# Register.net
KiCad netlist of a schematic drawn in EAGLE
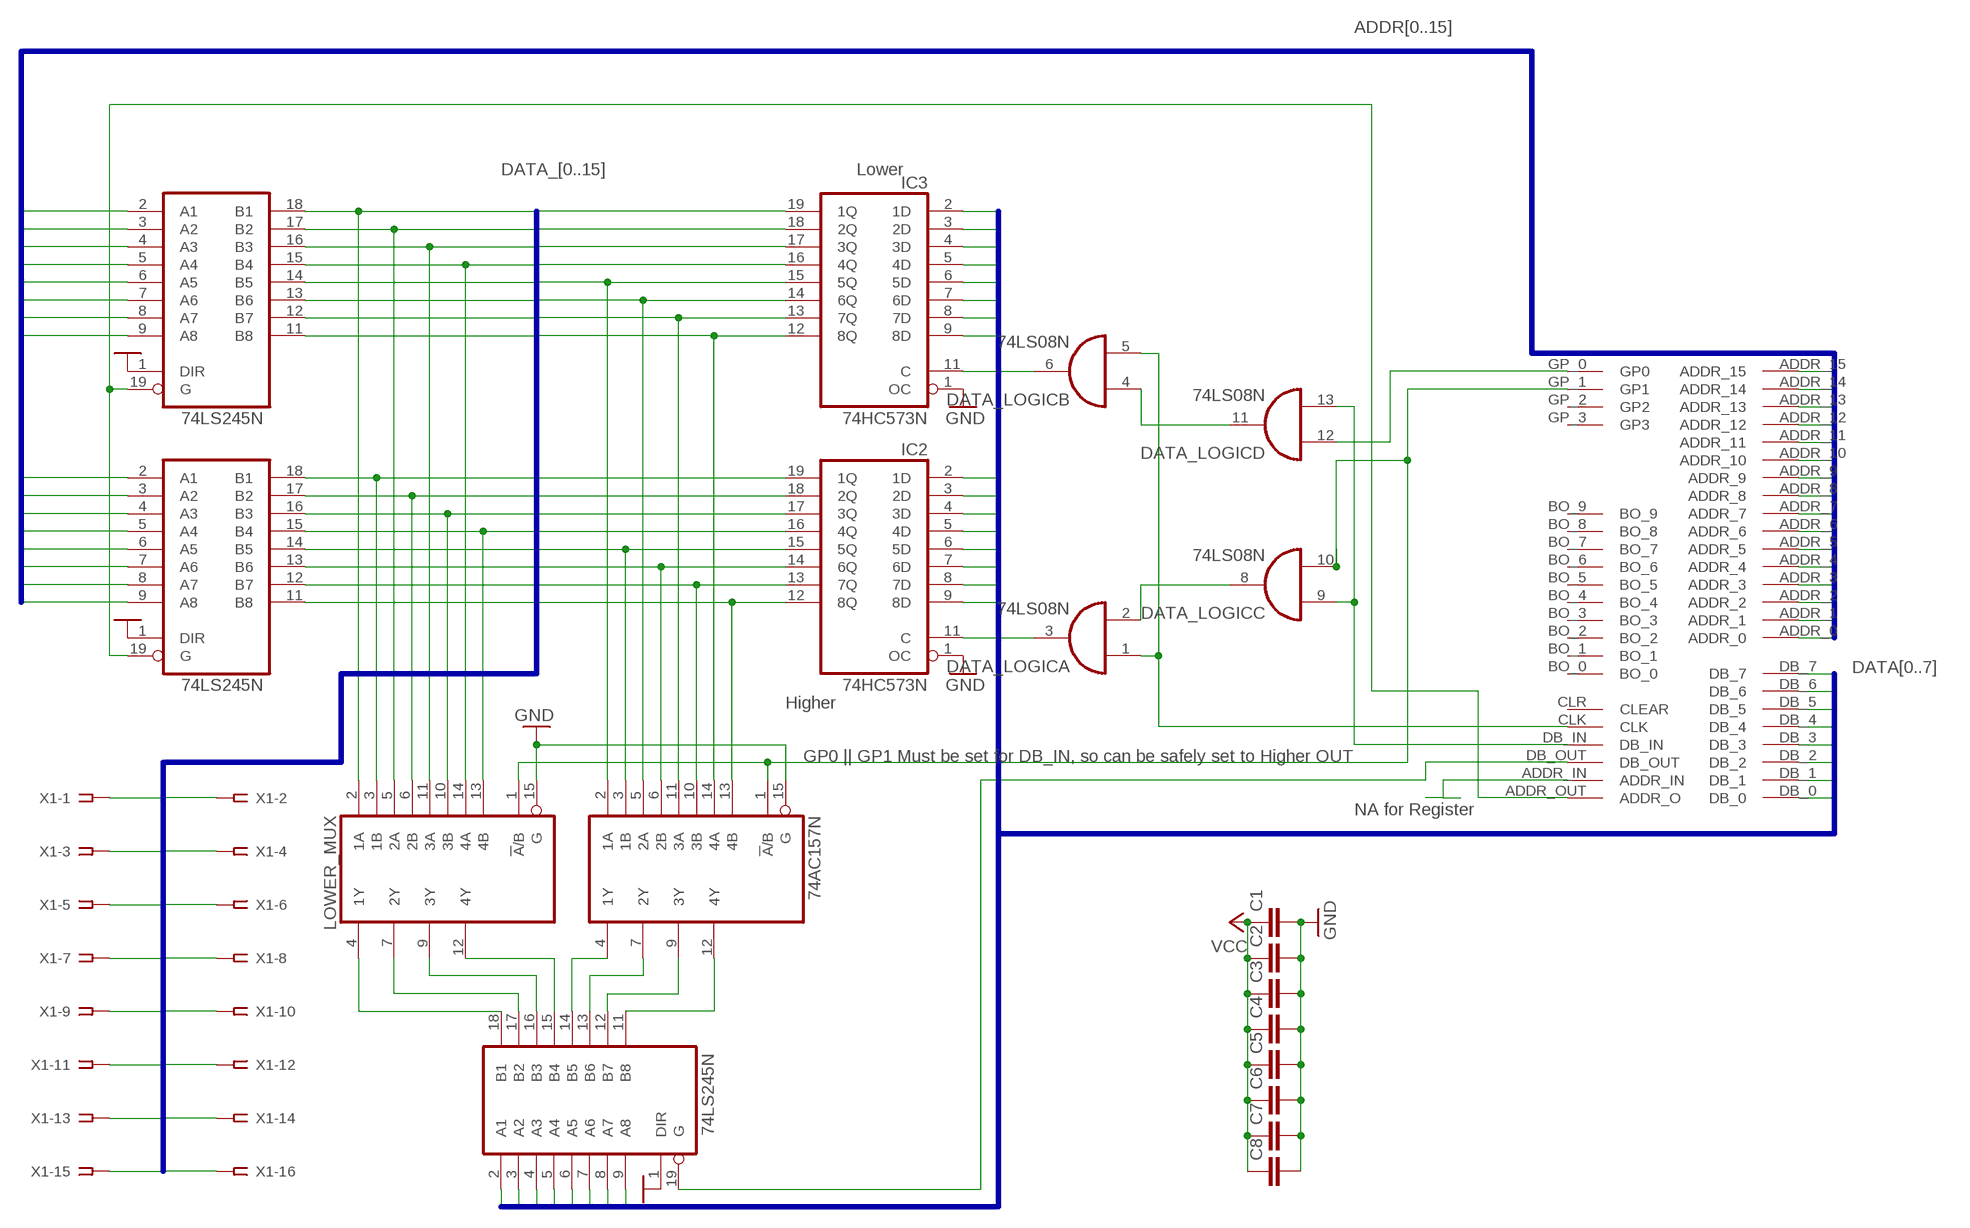
[diagram p0: schematic, sheet 1]

(export (version "E")
  (design (tool "Eeschema 10.0.6"))
  (components
    (comp (ref "ADDR_HIGHER_BUFFER")
      (value "74LS245N")
      (footprint "eagle-import:DIL20")
      (libsource (lib "eagle-import") (part "74245NLS"))
    )
    (comp (ref "ADDR_LOWER_BUFFER")
      (value "74LS245N")
      (footprint "eagle-import:DIL20")
      (libsource (lib "eagle-import") (part "74245NLS"))
    )
    (comp (ref "C1")
      (value "C2.5/2")
      (footprint "eagle-import:C2.5-2")
      (libsource (lib "eagle-import") (part "C2.5/2"))
    )
    (comp (ref "C2")
      (value "C2.5/2")
      (footprint "eagle-import:C2.5-2")
      (libsource (lib "eagle-import") (part "C2.5/2"))
    )
    (comp (ref "C3")
      (value "C2.5/2")
      (footprint "eagle-import:C2.5-2")
      (libsource (lib "eagle-import") (part "C2.5/2"))
    )
    (comp (ref "C4")
      (value "C2.5/2")
      (footprint "eagle-import:C2.5-2")
      (libsource (lib "eagle-import") (part "C2.5/2"))
    )
    (comp (ref "C5")
      (value "C2.5/2")
      (footprint "eagle-import:C2.5-2")
      (libsource (lib "eagle-import") (part "C2.5/2"))
    )
    (comp (ref "C6")
      (value "C2.5/2")
      (footprint "eagle-import:C2.5-2")
      (libsource (lib "eagle-import") (part "C2.5/2"))
    )
    (comp (ref "C7")
      (value "C2.5/2")
      (footprint "eagle-import:C2.5-2")
      (libsource (lib "eagle-import") (part "C2.5/2"))
    )
    (comp (ref "C8")
      (value "C2.5/2")
      (footprint "eagle-import:C2.5-2")
      (libsource (lib "eagle-import") (part "C2.5/2"))
    )
    (comp (ref "DATA_LOGIC")
      (value "74LS08N")
      (footprint "eagle-import:DIL14")
      (libsource (lib "eagle-import") (part "7408NLS"))
    )
    (comp (ref "DATA_OUTPUT_BUFFER")
      (value "74LS245N")
      (footprint "eagle-import:DIL20")
      (libsource (lib "eagle-import") (part "74245NLS"))
    )
    (comp (ref "HIGHER_MUX")
      (value "74AC157N")
      (footprint "eagle-import:DIL16")
      (libsource (lib "eagle-import") (part "74157NAC"))
    )
    (comp (ref "IC2")
      (value "74HC573N")
      (footprint "eagle-import:DIL20")
      (libsource (lib "eagle-import") (part "74573NHC"))
    )
    (comp (ref "IC3")
      (value "74HC573N")
      (footprint "eagle-import:DIL20")
      (libsource (lib "eagle-import") (part "74573NHC"))
    )
    (comp (ref "LOWER_MUX")
      (value "74AC157N")
      (footprint "eagle-import:DIL16")
      (libsource (lib "eagle-import") (part "74157NAC"))
    )
    (comp (ref "U$1")
      (value "BACKPLATE_INTERFACEEDGE_FINGER")
      (footprint "eagle-import:BACK_INTERFACE-FOOT")
      (libsource (lib "eagle-import") (part "BACKPLATE_INTERFACEEDGE_FINGER"))
    )
    (comp (ref "X1")
      (value "SSW-108-02-G-D")
      (footprint "eagle-import:SSW-108-02-G-D")
      (fields (field (name "MF") "Samtec Inc."))
      (libsource (lib "eagle-import") (part "SSW-108-02-G-D"))
    )
  )
  (nets
    (net (code "1") (name "/ADDR0") (class "Default")
      (node (ref "ADDR_LOWER_BUFFER") (pin "2") (pinfunction "A1_2") (pintype "bidirectional"))
      (node (ref "U$1") (pin "ADDR_0") (pinfunction "ADDR_0_ADDR_0") (pintype "bidirectional"))
    )
    (net (code "2") (name "/ADDR1") (class "Default")
      (node (ref "ADDR_LOWER_BUFFER") (pin "3") (pinfunction "A2_3") (pintype "bidirectional"))
      (node (ref "U$1") (pin "ADDR_1") (pinfunction "ADDR_1_ADDR_1") (pintype "bidirectional"))
    )
    (net (code "3") (name "/ADDR2") (class "Default")
      (node (ref "ADDR_LOWER_BUFFER") (pin "4") (pinfunction "A3_4") (pintype "bidirectional"))
      (node (ref "U$1") (pin "ADDR_2") (pinfunction "ADDR_2_ADDR_2") (pintype "bidirectional"))
    )
    (net (code "4") (name "/ADDR3") (class "Default")
      (node (ref "ADDR_LOWER_BUFFER") (pin "5") (pinfunction "A4_5") (pintype "bidirectional"))
      (node (ref "U$1") (pin "ADDR_3") (pinfunction "ADDR_3_ADDR_3") (pintype "bidirectional"))
    )
    (net (code "5") (name "/ADDR4") (class "Default")
      (node (ref "ADDR_LOWER_BUFFER") (pin "6") (pinfunction "A5_6") (pintype "bidirectional"))
      (node (ref "U$1") (pin "ADDR_4") (pinfunction "ADDR_4_ADDR_4") (pintype "bidirectional"))
    )
    (net (code "6") (name "/ADDR5") (class "Default")
      (node (ref "ADDR_LOWER_BUFFER") (pin "7") (pinfunction "A6_7") (pintype "bidirectional"))
      (node (ref "U$1") (pin "ADDR_5") (pinfunction "ADDR_5_ADDR_5") (pintype "bidirectional"))
    )
    (net (code "7") (name "/ADDR6") (class "Default")
      (node (ref "ADDR_LOWER_BUFFER") (pin "8") (pinfunction "A7_8") (pintype "bidirectional"))
      (node (ref "U$1") (pin "ADDR_6") (pinfunction "ADDR_6_ADDR_6") (pintype "bidirectional"))
    )
    (net (code "8") (name "/ADDR7") (class "Default")
      (node (ref "ADDR_LOWER_BUFFER") (pin "9") (pinfunction "A8_9") (pintype "bidirectional"))
      (node (ref "U$1") (pin "ADDR_7") (pinfunction "ADDR_7_ADDR_7") (pintype "bidirectional"))
    )
    (net (code "9") (name "/ADDR8") (class "Default")
      (node (ref "ADDR_HIGHER_BUFFER") (pin "2") (pinfunction "A1_2") (pintype "bidirectional"))
      (node (ref "U$1") (pin "ADDR_8") (pinfunction "ADDR_8_ADDR_8") (pintype "bidirectional"))
    )
    (net (code "10") (name "/ADDR9") (class "Default")
      (node (ref "ADDR_HIGHER_BUFFER") (pin "3") (pinfunction "A2_3") (pintype "bidirectional"))
      (node (ref "U$1") (pin "ADDR_9") (pinfunction "ADDR_9_ADDR_9") (pintype "bidirectional"))
    )
    (net (code "11") (name "/ADDR10") (class "Default")
      (node (ref "ADDR_HIGHER_BUFFER") (pin "4") (pinfunction "A3_4") (pintype "bidirectional"))
      (node (ref "U$1") (pin "ADDR_10") (pinfunction "ADDR_10_ADDR_10") (pintype "bidirectional"))
    )
    (net (code "12") (name "/ADDR11") (class "Default")
      (node (ref "ADDR_HIGHER_BUFFER") (pin "5") (pinfunction "A4_5") (pintype "bidirectional"))
      (node (ref "U$1") (pin "ADDR_11") (pinfunction "ADDR_11_ADDR_11") (pintype "bidirectional"))
    )
    (net (code "13") (name "/ADDR12") (class "Default")
      (node (ref "ADDR_HIGHER_BUFFER") (pin "6") (pinfunction "A5_6") (pintype "bidirectional"))
      (node (ref "U$1") (pin "ADDR_12") (pinfunction "ADDR_12_ADDR_12") (pintype "bidirectional"))
    )
    (net (code "14") (name "/ADDR13") (class "Default")
      (node (ref "ADDR_HIGHER_BUFFER") (pin "7") (pinfunction "A6_7") (pintype "bidirectional"))
      (node (ref "U$1") (pin "ADDR_13") (pinfunction "ADDR_13_ADDR_13") (pintype "bidirectional"))
    )
    (net (code "15") (name "/ADDR14") (class "Default")
      (node (ref "ADDR_HIGHER_BUFFER") (pin "8") (pinfunction "A7_8") (pintype "bidirectional"))
      (node (ref "U$1") (pin "ADDR_14") (pinfunction "ADDR_14_ADDR_14") (pintype "bidirectional"))
    )
    (net (code "16") (name "/ADDR15") (class "Default")
      (node (ref "ADDR_HIGHER_BUFFER") (pin "9") (pinfunction "A8_9") (pintype "bidirectional"))
      (node (ref "U$1") (pin "ADDR_15") (pinfunction "ADDR_15_ADDR_15") (pintype "bidirectional"))
    )
    (net (code "18") (name "/DATA0") (class "Default")
      (node (ref "DATA_OUTPUT_BUFFER") (pin "2") (pinfunction "A1_2") (pintype "bidirectional"))
      (node (ref "IC2") (pin "2") (pinfunction "1D_2") (pintype "input"))
      (node (ref "IC3") (pin "2") (pinfunction "1D_2") (pintype "input"))
      (node (ref "U$1") (pin "DB_0") (pinfunction "DB_0_DB_0") (pintype "bidirectional"))
    )
    (net (code "19") (name "/DATA1") (class "Default")
      (node (ref "DATA_OUTPUT_BUFFER") (pin "3") (pinfunction "A2_3") (pintype "bidirectional"))
      (node (ref "IC2") (pin "3") (pinfunction "2D_3") (pintype "input"))
      (node (ref "IC3") (pin "3") (pinfunction "2D_3") (pintype "input"))
      (node (ref "U$1") (pin "DB_1") (pinfunction "DB_1_DB_1") (pintype "bidirectional"))
    )
    (net (code "20") (name "/DATA2") (class "Default")
      (node (ref "DATA_OUTPUT_BUFFER") (pin "4") (pinfunction "A3_4") (pintype "bidirectional"))
      (node (ref "IC2") (pin "4") (pinfunction "3D_4") (pintype "input"))
      (node (ref "IC3") (pin "4") (pinfunction "3D_4") (pintype "input"))
      (node (ref "U$1") (pin "DB_2") (pinfunction "DB_2_DB_2") (pintype "bidirectional"))
    )
    (net (code "21") (name "/DATA3") (class "Default")
      (node (ref "DATA_OUTPUT_BUFFER") (pin "5") (pinfunction "A4_5") (pintype "bidirectional"))
      (node (ref "IC2") (pin "5") (pinfunction "4D_5") (pintype "input"))
      (node (ref "IC3") (pin "5") (pinfunction "4D_5") (pintype "input"))
      (node (ref "U$1") (pin "DB_3") (pinfunction "DB_3_DB_3") (pintype "bidirectional"))
    )
    (net (code "22") (name "/DATA4") (class "Default")
      (node (ref "DATA_OUTPUT_BUFFER") (pin "6") (pinfunction "A5_6") (pintype "bidirectional"))
      (node (ref "IC2") (pin "6") (pinfunction "5D_6") (pintype "input"))
      (node (ref "IC3") (pin "6") (pinfunction "5D_6") (pintype "input"))
      (node (ref "U$1") (pin "DB_4") (pinfunction "DB_4_DB_4") (pintype "bidirectional"))
    )
    (net (code "23") (name "/DATA5") (class "Default")
      (node (ref "DATA_OUTPUT_BUFFER") (pin "7") (pinfunction "A6_7") (pintype "bidirectional"))
      (node (ref "IC2") (pin "7") (pinfunction "6D_7") (pintype "input"))
      (node (ref "IC3") (pin "7") (pinfunction "6D_7") (pintype "input"))
      (node (ref "U$1") (pin "DB_5") (pinfunction "DB_5_DB_5") (pintype "bidirectional"))
    )
    (net (code "24") (name "/DATA6") (class "Default")
      (node (ref "DATA_OUTPUT_BUFFER") (pin "8") (pinfunction "A7_8") (pintype "bidirectional"))
      (node (ref "IC2") (pin "8") (pinfunction "7D_8") (pintype "input"))
      (node (ref "IC3") (pin "8") (pinfunction "7D_8") (pintype "input"))
      (node (ref "U$1") (pin "DB_6") (pinfunction "DB_6_DB_6") (pintype "bidirectional"))
    )
    (net (code "25") (name "/DATA7") (class "Default")
      (node (ref "DATA_OUTPUT_BUFFER") (pin "9") (pinfunction "A8_9") (pintype "bidirectional"))
      (node (ref "IC2") (pin "9") (pinfunction "8D_9") (pintype "input"))
      (node (ref "IC3") (pin "9") (pinfunction "8D_9") (pintype "input"))
      (node (ref "U$1") (pin "DB_7") (pinfunction "DB_7_DB_7") (pintype "bidirectional"))
    )
    (net (code "27") (name "/DATA_0") (class "Default")
      (node (ref "ADDR_LOWER_BUFFER") (pin "18") (pinfunction "B1_18") (pintype "bidirectional"))
      (node (ref "IC3") (pin "19") (pinfunction "1Q_19") (pintype "tri_state"))
      (node (ref "LOWER_MUX") (pin "2") (pinfunction "1A_2") (pintype "input"))
      (node (ref "X1") (pin "15") (pinfunction "1_15") (pintype "passive"))
    )
    (net (code "28") (name "/DATA_1") (class "Default")
      (node (ref "ADDR_LOWER_BUFFER") (pin "17") (pinfunction "B2_17") (pintype "bidirectional"))
      (node (ref "IC3") (pin "18") (pinfunction "2Q_18") (pintype "tri_state"))
      (node (ref "LOWER_MUX") (pin "5") (pinfunction "2A_5") (pintype "input"))
      (node (ref "X1") (pin "13") (pinfunction "1_13") (pintype "passive"))
    )
    (net (code "29") (name "/DATA_2") (class "Default")
      (node (ref "ADDR_LOWER_BUFFER") (pin "16") (pinfunction "B3_16") (pintype "bidirectional"))
      (node (ref "IC3") (pin "17") (pinfunction "3Q_17") (pintype "tri_state"))
      (node (ref "LOWER_MUX") (pin "11") (pinfunction "3A_11") (pintype "input"))
      (node (ref "X1") (pin "11") (pinfunction "1_11") (pintype "passive"))
    )
    (net (code "30") (name "/DATA_3") (class "Default")
      (node (ref "ADDR_LOWER_BUFFER") (pin "15") (pinfunction "B4_15") (pintype "bidirectional"))
      (node (ref "IC3") (pin "16") (pinfunction "4Q_16") (pintype "tri_state"))
      (node (ref "LOWER_MUX") (pin "14") (pinfunction "4A_14") (pintype "input"))
      (node (ref "X1") (pin "9") (pinfunction "1_9") (pintype "passive"))
    )
    (net (code "31") (name "/DATA_4") (class "Default")
      (node (ref "ADDR_LOWER_BUFFER") (pin "14") (pinfunction "B5_14") (pintype "bidirectional"))
      (node (ref "HIGHER_MUX") (pin "2") (pinfunction "1A_2") (pintype "input"))
      (node (ref "IC3") (pin "15") (pinfunction "5Q_15") (pintype "tri_state"))
      (node (ref "X1") (pin "7") (pinfunction "1_7") (pintype "passive"))
    )
    (net (code "32") (name "/DATA_5") (class "Default")
      (node (ref "ADDR_LOWER_BUFFER") (pin "13") (pinfunction "B6_13") (pintype "bidirectional"))
      (node (ref "HIGHER_MUX") (pin "5") (pinfunction "2A_5") (pintype "input"))
      (node (ref "IC3") (pin "14") (pinfunction "6Q_14") (pintype "tri_state"))
      (node (ref "X1") (pin "5") (pinfunction "1_5") (pintype "passive"))
    )
    (net (code "33") (name "/DATA_6") (class "Default")
      (node (ref "ADDR_LOWER_BUFFER") (pin "12") (pinfunction "B7_12") (pintype "bidirectional"))
      (node (ref "HIGHER_MUX") (pin "11") (pinfunction "3A_11") (pintype "input"))
      (node (ref "IC3") (pin "13") (pinfunction "7Q_13") (pintype "tri_state"))
      (node (ref "X1") (pin "3") (pinfunction "1_3") (pintype "passive"))
    )
    (net (code "34") (name "/DATA_7") (class "Default")
      (node (ref "ADDR_LOWER_BUFFER") (pin "11") (pinfunction "B8_11") (pintype "bidirectional"))
      (node (ref "HIGHER_MUX") (pin "14") (pinfunction "4A_14") (pintype "input"))
      (node (ref "IC3") (pin "12") (pinfunction "8Q_12") (pintype "tri_state"))
      (node (ref "X1") (pin "1") (pinfunction "1_1") (pintype "passive"))
    )
    (net (code "35") (name "/DATA_8") (class "Default")
      (node (ref "ADDR_HIGHER_BUFFER") (pin "18") (pinfunction "B1_18") (pintype "bidirectional"))
      (node (ref "IC2") (pin "19") (pinfunction "1Q_19") (pintype "tri_state"))
      (node (ref "LOWER_MUX") (pin "3") (pinfunction "1B_3") (pintype "input"))
      (node (ref "X1") (pin "2") (pinfunction "1_2") (pintype "passive"))
    )
    (net (code "36") (name "/DATA_9") (class "Default")
      (node (ref "ADDR_HIGHER_BUFFER") (pin "17") (pinfunction "B2_17") (pintype "bidirectional"))
      (node (ref "IC2") (pin "18") (pinfunction "2Q_18") (pintype "tri_state"))
      (node (ref "LOWER_MUX") (pin "6") (pinfunction "2B_6") (pintype "input"))
      (node (ref "X1") (pin "4") (pinfunction "1_4") (pintype "passive"))
    )
    (net (code "37") (name "/DATA_10") (class "Default")
      (node (ref "ADDR_HIGHER_BUFFER") (pin "16") (pinfunction "B3_16") (pintype "bidirectional"))
      (node (ref "IC2") (pin "17") (pinfunction "3Q_17") (pintype "tri_state"))
      (node (ref "LOWER_MUX") (pin "10") (pinfunction "3B_10") (pintype "input"))
      (node (ref "X1") (pin "6") (pinfunction "1_6") (pintype "passive"))
    )
    (net (code "38") (name "/DATA_11") (class "Default")
      (node (ref "ADDR_HIGHER_BUFFER") (pin "15") (pinfunction "B4_15") (pintype "bidirectional"))
      (node (ref "IC2") (pin "16") (pinfunction "4Q_16") (pintype "tri_state"))
      (node (ref "LOWER_MUX") (pin "13") (pinfunction "4B_13") (pintype "input"))
      (node (ref "X1") (pin "8") (pinfunction "1_8") (pintype "passive"))
    )
    (net (code "39") (name "/DATA_12") (class "Default")
      (node (ref "ADDR_HIGHER_BUFFER") (pin "14") (pinfunction "B5_14") (pintype "bidirectional"))
      (node (ref "HIGHER_MUX") (pin "3") (pinfunction "1B_3") (pintype "input"))
      (node (ref "IC2") (pin "15") (pinfunction "5Q_15") (pintype "tri_state"))
      (node (ref "X1") (pin "10") (pinfunction "1_10") (pintype "passive"))
    )
    (net (code "40") (name "/DATA_13") (class "Default")
      (node (ref "ADDR_HIGHER_BUFFER") (pin "13") (pinfunction "B6_13") (pintype "bidirectional"))
      (node (ref "HIGHER_MUX") (pin "6") (pinfunction "2B_6") (pintype "input"))
      (node (ref "IC2") (pin "14") (pinfunction "6Q_14") (pintype "tri_state"))
      (node (ref "X1") (pin "12") (pinfunction "1_12") (pintype "passive"))
    )
    (net (code "41") (name "/DATA_14") (class "Default")
      (node (ref "ADDR_HIGHER_BUFFER") (pin "12") (pinfunction "B7_12") (pintype "bidirectional"))
      (node (ref "HIGHER_MUX") (pin "10") (pinfunction "3B_10") (pintype "input"))
      (node (ref "IC2") (pin "13") (pinfunction "7Q_13") (pintype "tri_state"))
      (node (ref "X1") (pin "14") (pinfunction "1_14") (pintype "passive"))
    )
    (net (code "42") (name "/DATA_15") (class "Default")
      (node (ref "ADDR_HIGHER_BUFFER") (pin "11") (pinfunction "B8_11") (pintype "bidirectional"))
      (node (ref "HIGHER_MUX") (pin "13") (pinfunction "4B_13") (pintype "input"))
      (node (ref "IC2") (pin "12") (pinfunction "8Q_12") (pintype "tri_state"))
      (node (ref "X1") (pin "16") (pinfunction "1_16") (pintype "passive"))
    )
    (net (code "43") (name "GND") (class "Default")
      (node (ref "ADDR_HIGHER_BUFFER") (pin "1") (pinfunction "DIR_1") (pintype "input"))
      (node (ref "ADDR_LOWER_BUFFER") (pin "1") (pinfunction "DIR_1") (pintype "input"))
      (node (ref "C1") (pin "2") (pinfunction "2_2") (pintype "passive"))
      (node (ref "C2") (pin "2") (pinfunction "2_2") (pintype "passive"))
      (node (ref "C3") (pin "2") (pinfunction "2_2") (pintype "passive"))
      (node (ref "C4") (pin "2") (pinfunction "2_2") (pintype "passive"))
      (node (ref "C5") (pin "2") (pinfunction "2_2") (pintype "passive"))
      (node (ref "C6") (pin "2") (pinfunction "2_2") (pintype "passive"))
      (node (ref "C7") (pin "2") (pinfunction "2_2") (pintype "passive"))
      (node (ref "C8") (pin "2") (pinfunction "2_2") (pintype "passive"))
      (node (ref "DATA_OUTPUT_BUFFER") (pin "1") (pinfunction "DIR_1") (pintype "input"))
      (node (ref "HIGHER_MUX") (pin "15") (pinfunction "G_15") (pintype "input"))
      (node (ref "IC2") (pin "1") (pinfunction "OC_1") (pintype "input"))
      (node (ref "IC3") (pin "1") (pinfunction "OC_1") (pintype "input"))
      (node (ref "LOWER_MUX") (pin "15") (pinfunction "G_15") (pintype "input"))
    )
    (net (code "44") (name "Net-(ADDR_HIGHER_BUFFERA-G)") (class "Default")
      (node (ref "ADDR_HIGHER_BUFFER") (pin "19") (pinfunction "G_19") (pintype "input"))
      (node (ref "ADDR_LOWER_BUFFER") (pin "19") (pinfunction "G_19") (pintype "input"))
      (node (ref "U$1") (pin "ADDR_OUT") (pinfunction "ADDR_O_ADDR_OUT") (pintype "bidirectional"))
    )
    (net (code "45") (name "Net-(DATA_LOGICA-I0)") (class "Default")
      (node (ref "DATA_LOGIC") (pin "1") (pinfunction "I0_1") (pintype "input"))
      (node (ref "DATA_LOGIC") (pin "5") (pinfunction "I1_5") (pintype "input"))
      (node (ref "U$1") (pin "CLK") (pinfunction "CLK_CLK") (pintype "bidirectional"))
    )
    (net (code "46") (name "Net-(DATA_LOGICA-I1)") (class "Default")
      (node (ref "DATA_LOGIC") (pin "2") (pinfunction "I1_2") (pintype "input"))
      (node (ref "DATA_LOGIC") (pin "8") (pinfunction "O_8") (pintype "output"))
    )
    (net (code "47") (name "Net-(DATA_LOGICA-O)") (class "Default")
      (node (ref "DATA_LOGIC") (pin "3") (pinfunction "O_3") (pintype "output"))
      (node (ref "IC2") (pin "11") (pinfunction "C_11") (pintype "input"))
    )
    (net (code "48") (name "Net-(DATA_LOGICB-I0)") (class "Default")
      (node (ref "DATA_LOGIC") (pin "11") (pinfunction "O_11") (pintype "output"))
      (node (ref "DATA_LOGIC") (pin "4") (pinfunction "I0_4") (pintype "input"))
    )
    (net (code "49") (name "Net-(DATA_LOGICB-O)") (class "Default")
      (node (ref "DATA_LOGIC") (pin "6") (pinfunction "O_6") (pintype "output"))
      (node (ref "IC3") (pin "11") (pinfunction "C_11") (pintype "input"))
    )
    (net (code "50") (name "Net-(DATA_LOGICC-I0)") (class "Default")
      (node (ref "DATA_LOGIC") (pin "13") (pinfunction "I1_13") (pintype "input"))
      (node (ref "DATA_LOGIC") (pin "9") (pinfunction "I0_9") (pintype "input"))
      (node (ref "U$1") (pin "DB_IN") (pinfunction "DB_IN_DB_IN") (pintype "bidirectional"))
    )
    (net (code "51") (name "Net-(DATA_LOGICC-I1)") (class "Default")
      (node (ref "DATA_LOGIC") (pin "10") (pinfunction "I1_10") (pintype "input"))
      (node (ref "HIGHER_MUX") (pin "1") (pinfunction "~{A}/B_1") (pintype "input"))
      (node (ref "LOWER_MUX") (pin "1") (pinfunction "~{A}/B_1") (pintype "input"))
      (node (ref "U$1") (pin "GP_1") (pinfunction "GP1_GP_1") (pintype "bidirectional"))
    )
    (net (code "52") (name "Net-(DATA_LOGICD-I0)") (class "Default")
      (node (ref "DATA_LOGIC") (pin "12") (pinfunction "I0_12") (pintype "input"))
      (node (ref "U$1") (pin "GP_0") (pinfunction "GP0_GP_0") (pintype "bidirectional"))
    )
    (net (code "53") (name "Net-(DATA_OUTPUT_BUFFERA-B1)") (class "Default")
      (node (ref "DATA_OUTPUT_BUFFER") (pin "18") (pinfunction "B1_18") (pintype "bidirectional"))
      (node (ref "LOWER_MUX") (pin "4") (pinfunction "1Y_4") (pintype "output"))
    )
    (net (code "54") (name "Net-(DATA_OUTPUT_BUFFERA-B2)") (class "Default")
      (node (ref "DATA_OUTPUT_BUFFER") (pin "17") (pinfunction "B2_17") (pintype "bidirectional"))
      (node (ref "LOWER_MUX") (pin "7") (pinfunction "2Y_7") (pintype "output"))
    )
    (net (code "55") (name "Net-(DATA_OUTPUT_BUFFERA-B3)") (class "Default")
      (node (ref "DATA_OUTPUT_BUFFER") (pin "16") (pinfunction "B3_16") (pintype "bidirectional"))
      (node (ref "LOWER_MUX") (pin "9") (pinfunction "3Y_9") (pintype "output"))
    )
    (net (code "56") (name "Net-(DATA_OUTPUT_BUFFERA-B4)") (class "Default")
      (node (ref "DATA_OUTPUT_BUFFER") (pin "15") (pinfunction "B4_15") (pintype "bidirectional"))
      (node (ref "LOWER_MUX") (pin "12") (pinfunction "4Y_12") (pintype "output"))
    )
    (net (code "57") (name "Net-(DATA_OUTPUT_BUFFERA-B5)") (class "Default")
      (node (ref "DATA_OUTPUT_BUFFER") (pin "14") (pinfunction "B5_14") (pintype "bidirectional"))
      (node (ref "HIGHER_MUX") (pin "4") (pinfunction "1Y_4") (pintype "output"))
    )
    (net (code "58") (name "Net-(DATA_OUTPUT_BUFFERA-B6)") (class "Default")
      (node (ref "DATA_OUTPUT_BUFFER") (pin "13") (pinfunction "B6_13") (pintype "bidirectional"))
      (node (ref "HIGHER_MUX") (pin "7") (pinfunction "2Y_7") (pintype "output"))
    )
    (net (code "59") (name "Net-(DATA_OUTPUT_BUFFERA-B7)") (class "Default")
      (node (ref "DATA_OUTPUT_BUFFER") (pin "12") (pinfunction "B7_12") (pintype "bidirectional"))
      (node (ref "HIGHER_MUX") (pin "9") (pinfunction "3Y_9") (pintype "output"))
    )
    (net (code "60") (name "Net-(DATA_OUTPUT_BUFFERA-B8)") (class "Default")
      (node (ref "DATA_OUTPUT_BUFFER") (pin "11") (pinfunction "B8_11") (pintype "bidirectional"))
      (node (ref "HIGHER_MUX") (pin "12") (pinfunction "4Y_12") (pintype "output"))
    )
    (net (code "61") (name "Net-(DATA_OUTPUT_BUFFERA-G)") (class "Default")
      (node (ref "DATA_OUTPUT_BUFFER") (pin "19") (pinfunction "G_19") (pintype "input"))
      (node (ref "U$1") (pin "DB_OUT") (pinfunction "DB_OUT_DB_OUT") (pintype "bidirectional"))
    )
    (net (code "62") (name "VCC") (class "Default")
      (node (ref "C1") (pin "1") (pinfunction "1_1") (pintype "passive"))
      (node (ref "C2") (pin "1") (pinfunction "1_1") (pintype "passive"))
      (node (ref "C3") (pin "1") (pinfunction "1_1") (pintype "passive"))
      (node (ref "C4") (pin "1") (pinfunction "1_1") (pintype "passive"))
      (node (ref "C5") (pin "1") (pinfunction "1_1") (pintype "passive"))
      (node (ref "C6") (pin "1") (pinfunction "1_1") (pintype "passive"))
      (node (ref "C7") (pin "1") (pinfunction "1_1") (pintype "passive"))
      (node (ref "C8") (pin "1") (pinfunction "1_1") (pintype "passive"))
    )
    (net (code "63") (name "unconnected-(U$1-PadADDR_IN)") (class "Default")
      (node (ref "U$1") (pin "ADDR_IN") (pinfunction "ADDR_IN_ADDR_IN") (pintype "bidirectional"))
    )
    (net (code "64") (name "unconnected-(U$1-PadBO_0)") (class "Default")
      (node (ref "U$1") (pin "BO_0") (pinfunction "BO_0_BO_0") (pintype "bidirectional"))
    )
    (net (code "65") (name "unconnected-(U$1-PadBO_1)") (class "Default")
      (node (ref "U$1") (pin "BO_1") (pinfunction "BO_1_BO_1") (pintype "bidirectional"))
    )
    (net (code "66") (name "unconnected-(U$1-PadBO_2)") (class "Default")
      (node (ref "U$1") (pin "BO_2") (pinfunction "BO_2_BO_2") (pintype "bidirectional"))
    )
    (net (code "67") (name "unconnected-(U$1-PadBO_3)") (class "Default")
      (node (ref "U$1") (pin "BO_3") (pinfunction "BO_3_BO_3") (pintype "bidirectional"))
    )
    (net (code "68") (name "unconnected-(U$1-PadBO_4)") (class "Default")
      (node (ref "U$1") (pin "BO_4") (pinfunction "BO_4_BO_4") (pintype "bidirectional"))
    )
    (net (code "69") (name "unconnected-(U$1-PadBO_5)") (class "Default")
      (node (ref "U$1") (pin "BO_5") (pinfunction "BO_5_BO_5") (pintype "bidirectional"))
    )
    (net (code "70") (name "unconnected-(U$1-PadBO_6)") (class "Default")
      (node (ref "U$1") (pin "BO_6") (pinfunction "BO_6_BO_6") (pintype "bidirectional"))
    )
    (net (code "71") (name "unconnected-(U$1-PadBO_7)") (class "Default")
      (node (ref "U$1") (pin "BO_7") (pinfunction "BO_7_BO_7") (pintype "bidirectional"))
    )
    (net (code "72") (name "unconnected-(U$1-PadBO_8)") (class "Default")
      (node (ref "U$1") (pin "BO_8") (pinfunction "BO_8_BO_8") (pintype "bidirectional"))
    )
    (net (code "73") (name "unconnected-(U$1-PadBO_9)") (class "Default")
      (node (ref "U$1") (pin "BO_9") (pinfunction "BO_9_BO_9") (pintype "bidirectional"))
    )
    (net (code "74") (name "unconnected-(U$1A-CLEAR-PadCLR)") (class "Default")
      (node (ref "U$1") (pin "CLR") (pinfunction "CLEAR_CLR") (pintype "bidirectional"))
    )
    (net (code "75") (name "unconnected-(U$1A-GP2-PadGP_2)") (class "Default")
      (node (ref "U$1") (pin "GP_2") (pinfunction "GP2_GP_2") (pintype "bidirectional"))
    )
    (net (code "76") (name "unconnected-(U$1A-GP3-PadGP_3)") (class "Default")
      (node (ref "U$1") (pin "GP_3") (pinfunction "GP3_GP_3") (pintype "bidirectional"))
    )
  )
)
